# RIGHT_MOTOR.net
KiCad netlist of a schematic drawn in Altium Designer
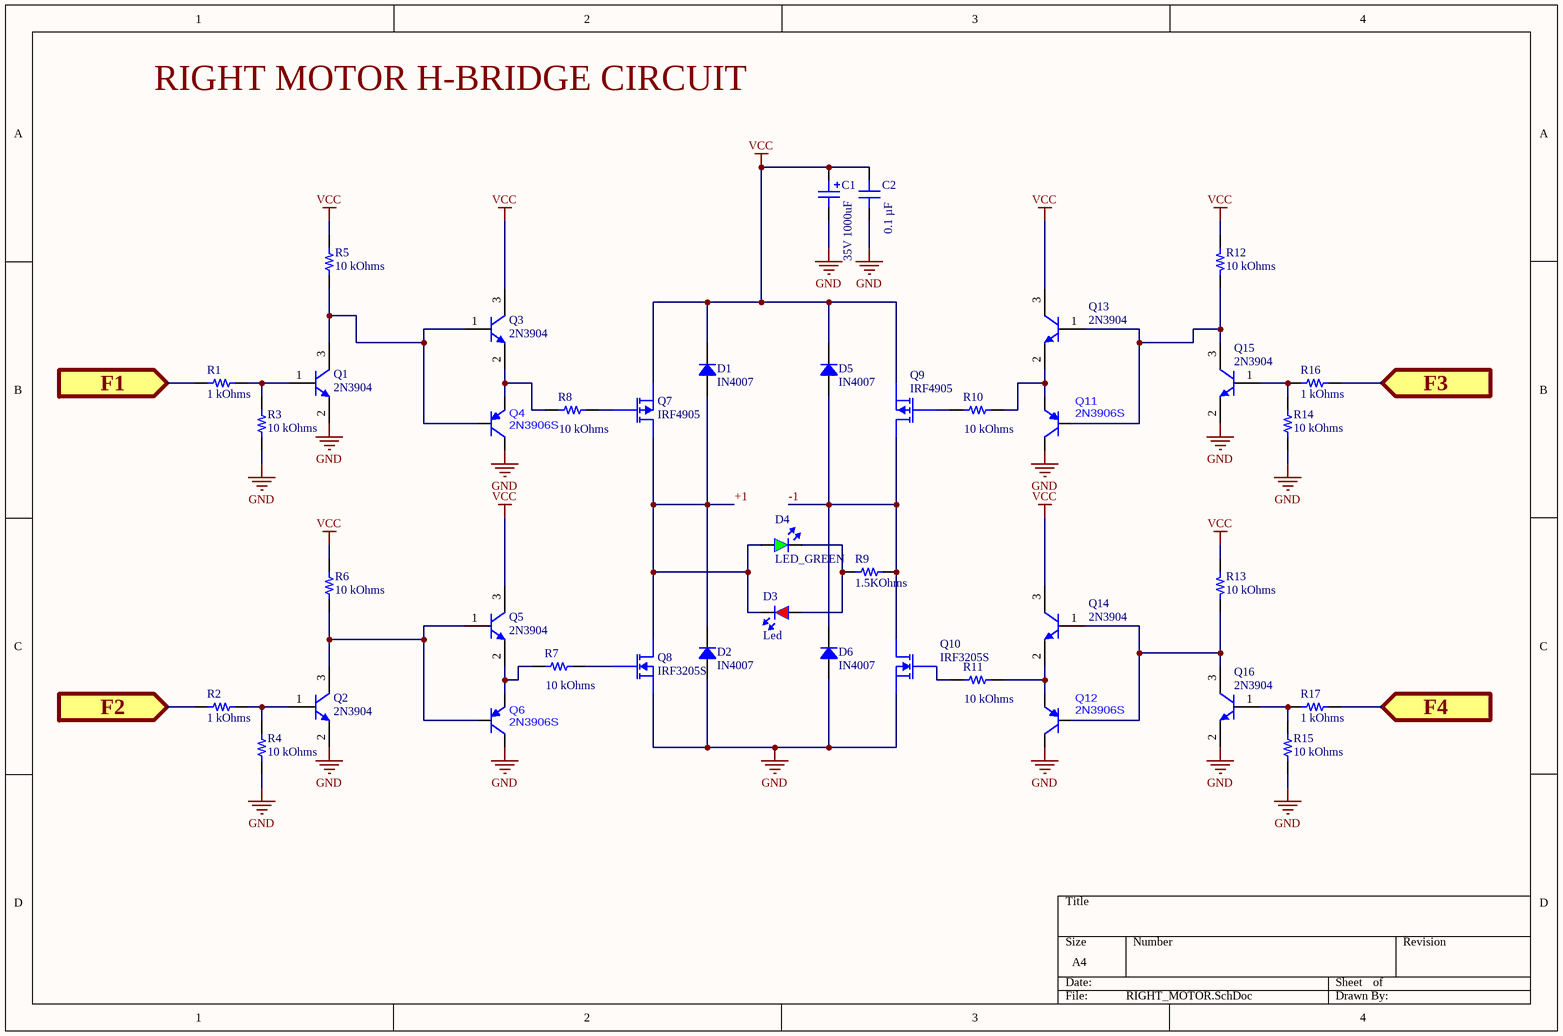
[diagram p0: RIGHT_MOTOR.SchDoc]

(export (version "E")
  (design (tool "Eeschema 10.0.6"))
  (components
    (comp (ref "C1") (value "35V 1000uF") (footprint "35V 1000uF") (libsource (lib "AS") (part "35V 1000uF")))
    (comp (ref "C2")
      (value "0.1 µF")
      (footprint "CAP 1210_3225 - 1MM")
      (description "1210 50VDC 100NF 10% X7R(2R1) AE")
      (fields (field (name "PART NUMBER") "1210Y0500104KST") (field (name "MANUFACTURER") "Knowles Syfer"))
      (libsource (lib "Celestial Altium Library - altium_library") (part "Capacitor"))
    )
    (comp (ref "D1")
      (value "IN4007")
      (footprint "DO214AC SMA")
      (description "DIODE GEN PURP 50V 1A SMA")
      (fields (field (name "PART NUMBER") "RS1A") (field (name "MANUFACTURER") "ON Semiconductor"))
      (libsource (lib "Celestial Altium Library - altium_library") (part "Diode"))
    )
    (comp (ref "D2")
      (value "IN4007")
      (footprint "DO214AC SMA")
      (description "DIODE GEN PURP 50V 1A SMA")
      (fields (field (name "PART NUMBER") "RS1A") (field (name "MANUFACTURER") "ON Semiconductor"))
      (libsource (lib "Celestial Altium Library - altium_library") (part "Diode"))
    )
    (comp (ref "D3") (value "Led") (footprint "LED_RED") (libsource (lib "HBRIDGE") (part "LED_RED_1")))
    (comp (ref "D4")
      (value "LED_GREEN")
      (footprint "LED_GREEN")
      (libsource (lib "HBRIDGE") (part "LED_GREEN"))
    )
    (comp (ref "D5")
      (value "IN4007")
      (footprint "DO214AC SMA")
      (description "DIODE GEN PURP 50V 1A SMA")
      (fields (field (name "PART NUMBER") "RS1A") (field (name "MANUFACTURER") "ON Semiconductor"))
      (libsource (lib "Celestial Altium Library - altium_library") (part "Diode"))
    )
    (comp (ref "D6")
      (value "IN4007")
      (footprint "DO214AC SMA")
      (description "DIODE GEN PURP 50V 1A SMA")
      (fields (field (name "PART NUMBER") "RS1A") (field (name "MANUFACTURER") "ON Semiconductor"))
      (libsource (lib "Celestial Altium Library - altium_library") (part "Diode"))
    )
    (comp (ref "Q1")
      (value "2N3904")
      (footprint "DIODES SOT-23-3")
      (description "2N3904 Npn Smd Transistör Sot-23")
      (fields (field (name "PART NUMBER") "MMBT3904-7-F") (field (name "MANUFACTURER") "Diodes Incorporated"))
      (libsource (lib "Celestial Altium Library - altium_library") (part "DIODES INC NPN SOT-23-3"))
    )
    (comp (ref "Q2")
      (value "2N3904")
      (footprint "DIODES SOT-23-3")
      (description "2N3904 Npn Smd Transistör Sot-23")
      (fields (field (name "PART NUMBER") "MMBT3904-7-F") (field (name "MANUFACTURER") "Diodes Incorporated"))
      (libsource (lib "Celestial Altium Library - altium_library") (part "DIODES INC NPN SOT-23-3"))
    )
    (comp (ref "Q3")
      (value "2N3904")
      (footprint "DIODES SOT-23-3")
      (description "2N3904 Npn Smd Transistör Sot-23")
      (fields (field (name "PART NUMBER") "MMBT3904-7-F") (field (name "MANUFACTURER") "Diodes Incorporated"))
      (libsource (lib "Celestial Altium Library - altium_library") (part "DIODES INC NPN SOT-23-3"))
    )
    (comp (ref "Q4") (value "2N3906S") (footprint "SOT23-3") (libsource (lib "") (part "2N3906S_1")))
    (comp (ref "Q5")
      (value "2N3904")
      (footprint "DIODES SOT-23-3")
      (description "2N3904 Npn Smd Transistör Sot-23")
      (fields (field (name "PART NUMBER") "MMBT3904-7-F") (field (name "MANUFACTURER") "Diodes Incorporated"))
      (libsource (lib "Celestial Altium Library - altium_library") (part "DIODES INC NPN SOT-23-3"))
    )
    (comp (ref "Q6") (value "2N3906S") (footprint "SOT23-3") (libsource (lib "") (part "2N3906S_1")))
    (comp (ref "Q7") (value "IRF4905") (footprint "IRF4905") (libsource (lib "AS") (part "IRF4905")))
    (comp (ref "Q8") (value "IRF3205S") (footprint "IRF3205S") (libsource (lib "HBRIDGE") (part "IRF3205S")))
    (comp (ref "Q9") (value "IRF4905") (footprint "IRF4905") (libsource (lib "AS") (part "IRF4905")))
    (comp (ref "Q10") (value "IRF3205S") (footprint "IRF3205S") (libsource (lib "") (part "IRF3205S_1")))
    (comp (ref "Q11") (value "2N3906S") (footprint "SOT23-3") (libsource (lib "HBRIDGE") (part "2N3906S")))
    (comp (ref "Q12") (value "2N3906S") (footprint "SOT23-3") (libsource (lib "HBRIDGE") (part "2N3906S")))
    (comp (ref "Q13")
      (value "2N3904")
      (footprint "DIODES SOT-23-3")
      (description "2N3904 Npn Smd Transistör Sot-23")
      (fields (field (name "PART NUMBER") "MMBT3904-7-F") (field (name "MANUFACTURER") "Diodes Incorporated"))
      (libsource (lib "Celestial Altium Library - altium_library") (part "DIODES INC NPN SOT-23-3"))
    )
    (comp (ref "Q14")
      (value "2N3904")
      (footprint "DIODES SOT-23-3")
      (description "2N3904 Npn Smd Transistör Sot-23")
      (fields (field (name "PART NUMBER") "MMBT3904-7-F") (field (name "MANUFACTURER") "Diodes Incorporated"))
      (libsource (lib "Celestial Altium Library - altium_library") (part "DIODES INC NPN SOT-23-3"))
    )
    (comp (ref "Q15")
      (value "2N3904")
      (footprint "DIODES SOT-23-3")
      (description "2N3904 Npn Smd Transistör Sot-23")
      (fields (field (name "PART NUMBER") "MMBT3904-7-F") (field (name "MANUFACTURER") "Diodes Incorporated"))
      (libsource (lib "Celestial Altium Library - altium_library") (part "DIODES INC NPN SOT-23-3"))
    )
    (comp (ref "Q16")
      (value "2N3904")
      (footprint "DIODES SOT-23-3")
      (description "2N3904 Npn Smd Transistör Sot-23")
      (fields (field (name "PART NUMBER") "MMBT3904-7-F") (field (name "MANUFACTURER") "Diodes Incorporated"))
      (libsource (lib "Celestial Altium Library - altium_library") (part "DIODES INC NPN SOT-23-3"))
    )
    (comp (ref "R1")
      (value "1 kOhms")
      (footprint "RES 1206_3216")
      (description "RES 1K OHM 0.1% 1/8W 1206")
      (fields
        (field (name "PART NUMBER") "RNCS1206BKE1K00")
        (field (name "MANUFACTURER") "Stackpole Electronics Inc")
      )
      (libsource (lib "Celestial Altium Library - altium_library") (part "Resistor"))
    )
    (comp (ref "R2")
      (value "1 kOhms")
      (footprint "RES 1206_3216")
      (description "RES 1K OHM 0.1% 1/8W 1206")
      (fields
        (field (name "PART NUMBER") "RNCS1206BKE1K00")
        (field (name "MANUFACTURER") "Stackpole Electronics Inc")
      )
      (libsource (lib "Celestial Altium Library - altium_library") (part "Resistor"))
    )
    (comp (ref "R3")
      (value "10 kOhms")
      (footprint "RES 1206_3216")
      (description "RES SMD 10K OHM 1% 1/4W 1206")
      (fields
        (field (name "PART NUMBER") "CRG1206F10K")
        (field (name "MANUFACTURER") "TE Connectivity Passive Product")
      )
      (libsource (lib "Celestial Altium Library - altium_library") (part "Resistor"))
    )
    (comp (ref "R4")
      (value "10 kOhms")
      (footprint "RES 1206_3216")
      (description "RES SMD 10K OHM 1% 1/4W 1206")
      (fields
        (field (name "PART NUMBER") "CRG1206F10K")
        (field (name "MANUFACTURER") "TE Connectivity Passive Product")
      )
      (libsource (lib "Celestial Altium Library - altium_library") (part "Resistor"))
    )
    (comp (ref "R5")
      (value "10 kOhms")
      (footprint "RES 1210_3225")
      (description "RES SMD 10K OHM 5% 3/4W 1210")
      (fields (field (name "PART NUMBER") "CRCW121010K0JNEAHP") (field (name "MANUFACTURER") "Vishay Dale"))
      (libsource (lib "Celestial Altium Library - altium_library") (part "Resistor"))
    )
    (comp (ref "R6")
      (value "10 kOhms")
      (footprint "RES 1210_3225")
      (description "RES SMD 10K OHM 5% 3/4W 1210")
      (fields (field (name "PART NUMBER") "CRCW121010K0JNEAHP") (field (name "MANUFACTURER") "Vishay Dale"))
      (libsource (lib "Celestial Altium Library - altium_library") (part "Resistor"))
    )
    (comp (ref "R7")
      (value "10 kOhms")
      (footprint "RES 1210_3225")
      (description "RES 10K OHM 1% 1/2W 1210")
      (fields
        (field (name "PART NUMBER") "RMCF1210FT10K0")
        (field (name "MANUFACTURER") "Stackpole Electronics Inc")
      )
      (libsource (lib "Celestial Altium Library - altium_library") (part "Resistor"))
    )
    (comp (ref "R8")
      (value "10 kOhms")
      (footprint "RES 1210_3225")
      (description "RES 10K OHM 1% 1/2W 1210")
      (fields
        (field (name "PART NUMBER") "RMCF1210FT10K0")
        (field (name "MANUFACTURER") "Stackpole Electronics Inc")
      )
      (libsource (lib "Celestial Altium Library - altium_library") (part "Resistor"))
    )
    (comp (ref "R9")
      (value "1.5KOhms")
      (footprint "RES 1210_3225")
      (description "RES 1.5K OHM 1% 1/2W 1210")
      (fields
        (field (name "PART NUMBER") "RMCF1210FT10K0")
        (field (name "MANUFACTURER") "Stackpole Electronics Inc")
      )
      (libsource (lib "Celestial Altium Library - altium_library") (part "Resistor"))
    )
    (comp (ref "R10")
      (value "10 kOhms")
      (footprint "RES 1210_3225")
      (description "RES 10K OHM 1% 1/2W 1210")
      (fields
        (field (name "PART NUMBER") "RMCF1210FT10K0")
        (field (name "MANUFACTURER") "Stackpole Electronics Inc")
      )
      (libsource (lib "Celestial Altium Library - altium_library") (part "Resistor"))
    )
    (comp (ref "R11")
      (value "10 kOhms")
      (footprint "RES 1210_3225")
      (description "RES 10K OHM 1% 1/2W 1210")
      (fields
        (field (name "PART NUMBER") "RMCF1210FT10K0")
        (field (name "MANUFACTURER") "Stackpole Electronics Inc")
      )
      (libsource (lib "Celestial Altium Library - altium_library") (part "Resistor"))
    )
    (comp (ref "R12")
      (value "10 kOhms")
      (footprint "RES 1210_3225")
      (description "RES SMD 10K OHM 5% 3/4W 1210")
      (fields (field (name "PART NUMBER") "CRCW121010K0JNEAHP") (field (name "MANUFACTURER") "Vishay Dale"))
      (libsource (lib "Celestial Altium Library - altium_library") (part "Resistor"))
    )
    (comp (ref "R13")
      (value "10 kOhms")
      (footprint "RES 1210_3225")
      (description "RES SMD 10K OHM 5% 3/4W 1210")
      (fields (field (name "PART NUMBER") "CRCW121010K0JNEAHP") (field (name "MANUFACTURER") "Vishay Dale"))
      (libsource (lib "Celestial Altium Library - altium_library") (part "Resistor"))
    )
    (comp (ref "R14")
      (value "10 kOhms")
      (footprint "RES 1206_3216")
      (description "RES SMD 10K OHM 1% 1/4W 1206")
      (fields
        (field (name "PART NUMBER") "CRG1206F10K")
        (field (name "MANUFACTURER") "TE Connectivity Passive Product")
      )
      (libsource (lib "Celestial Altium Library - altium_library") (part "Resistor"))
    )
    (comp (ref "R15")
      (value "10 kOhms")
      (footprint "RES 1206_3216")
      (description "RES SMD 10K OHM 1% 1/4W 1206")
      (fields
        (field (name "PART NUMBER") "CRG1206F10K")
        (field (name "MANUFACTURER") "TE Connectivity Passive Product")
      )
      (libsource (lib "Celestial Altium Library - altium_library") (part "Resistor"))
    )
    (comp (ref "R16")
      (value "1 kOhms")
      (footprint "RES 1206_3216")
      (description "RES 1K OHM 0.1% 1/8W 1206")
      (fields
        (field (name "PART NUMBER") "RNCS1206BKE1K00")
        (field (name "MANUFACTURER") "Stackpole Electronics Inc")
      )
      (libsource (lib "Celestial Altium Library - altium_library") (part "Resistor"))
    )
    (comp (ref "R17")
      (value "1 kOhms")
      (footprint "RES 1206_3216")
      (description "RES 1K OHM 0.1% 1/8W 1206")
      (fields
        (field (name "PART NUMBER") "RNCS1206BKE1K00")
        (field (name "MANUFACTURER") "Stackpole Electronics Inc")
      )
      (libsource (lib "Celestial Altium Library - altium_library") (part "Resistor"))
    )
  )
  (nets
    (net (code "1") (name "/+1") (class "Default")
      (node (ref "D1") (pin "1") (pinfunction "1_1") (pintype "passive"))
      (node (ref "D2") (pin "2") (pinfunction "2_2") (pintype "passive"))
      (node (ref "D3") (pin "2") (pinfunction "OUT_2") (pintype "passive"))
      (node (ref "D4") (pin "1") (pinfunction "IN_1") (pintype "passive"))
      (node (ref "Q7") (pin "2") (pinfunction "D_2") (pintype "passive"))
      (node (ref "Q8") (pin "2") (pinfunction "D_2") (pintype "passive"))
    )
    (net (code "2") (name "/-1") (class "Default")
      (node (ref "D5") (pin "1") (pinfunction "1_1") (pintype "passive"))
      (node (ref "D6") (pin "2") (pinfunction "2_2") (pintype "passive"))
      (node (ref "Q10") (pin "2") (pinfunction "D_2") (pintype "passive"))
      (node (ref "Q9") (pin "2") (pinfunction "D_2") (pintype "passive"))
      (node (ref "R9") (pin "2") (pinfunction "2_2") (pintype "passive"))
    )
    (net (code "3") (name "/F1") (class "Default")
      (node (ref "R1") (pin "1") (pinfunction "1_1") (pintype "passive"))
    )
    (net (code "4") (name "/F2") (class "Default")
      (node (ref "R2") (pin "1") (pinfunction "1_1") (pintype "passive"))
    )
    (net (code "5") (name "/F3") (class "Default")
      (node (ref "R16") (pin "2") (pinfunction "2_2") (pintype "passive"))
    )
    (net (code "6") (name "/F4") (class "Default")
      (node (ref "R17") (pin "2") (pinfunction "2_2") (pintype "passive"))
    )
    (net (code "8") (name "GND") (class "Default")
      (node (ref "C1") (pin "2") (pinfunction "out_2") (pintype "passive"))
      (node (ref "C2") (pin "1") (pinfunction "1_1") (pintype "passive"))
      (node (ref "D2") (pin "1") (pinfunction "1_1") (pintype "passive"))
      (node (ref "D6") (pin "1") (pinfunction "1_1") (pintype "passive"))
      (node (ref "Q1") (pin "2") (pinfunction "E_2") (pintype "passive"))
      (node (ref "Q10") (pin "3") (pinfunction "S_3") (pintype "passive"))
      (node (ref "Q11") (pin "3") (pinfunction "C_3") (pintype "passive"))
      (node (ref "Q12") (pin "3") (pinfunction "C_3") (pintype "passive"))
      (node (ref "Q15") (pin "2") (pinfunction "E_2") (pintype "passive"))
      (node (ref "Q16") (pin "2") (pinfunction "E_2") (pintype "passive"))
      (node (ref "Q2") (pin "2") (pinfunction "E_2") (pintype "passive"))
      (node (ref "Q4") (pin "3") (pinfunction "C_3") (pintype "passive"))
      (node (ref "Q6") (pin "3") (pinfunction "C_3") (pintype "passive"))
      (node (ref "Q8") (pin "3") (pinfunction "S_3") (pintype "passive"))
      (node (ref "R14") (pin "1") (pinfunction "1_1") (pintype "passive"))
      (node (ref "R15") (pin "1") (pinfunction "1_1") (pintype "passive"))
      (node (ref "R3") (pin "1") (pinfunction "1_1") (pintype "passive"))
      (node (ref "R4") (pin "1") (pinfunction "1_1") (pintype "passive"))
    )
    (net (code "9") (name "Net-(D3-IN)") (class "Default")
      (node (ref "D3") (pin "1") (pinfunction "IN_1") (pintype "passive"))
      (node (ref "D4") (pin "2") (pinfunction "OUT_2") (pintype "passive"))
      (node (ref "R9") (pin "1") (pinfunction "1_1") (pintype "passive"))
    )
    (net (code "10") (name "Net-(Q1-B)") (class "Default")
      (node (ref "Q1") (pin "1") (pinfunction "B_1") (pintype "passive"))
      (node (ref "R1") (pin "2") (pinfunction "2_2") (pintype "passive"))
      (node (ref "R3") (pin "2") (pinfunction "2_2") (pintype "passive"))
    )
    (net (code "11") (name "Net-(Q1-C)") (class "Default")
      (node (ref "Q1") (pin "3") (pinfunction "C_3") (pintype "passive"))
      (node (ref "Q3") (pin "1") (pinfunction "B_1") (pintype "passive"))
      (node (ref "Q4") (pin "1") (pinfunction "B_1") (pintype "passive"))
      (node (ref "R5") (pin "2") (pinfunction "2_2") (pintype "passive"))
    )
    (net (code "12") (name "Net-(Q2-B)") (class "Default")
      (node (ref "Q2") (pin "1") (pinfunction "B_1") (pintype "passive"))
      (node (ref "R2") (pin "2") (pinfunction "2_2") (pintype "passive"))
      (node (ref "R4") (pin "2") (pinfunction "2_2") (pintype "passive"))
    )
    (net (code "13") (name "Net-(Q2-C)") (class "Default")
      (node (ref "Q2") (pin "3") (pinfunction "C_3") (pintype "passive"))
      (node (ref "Q5") (pin "1") (pinfunction "B_1") (pintype "passive"))
      (node (ref "Q6") (pin "1") (pinfunction "B_1") (pintype "passive"))
      (node (ref "R6") (pin "2") (pinfunction "2_2") (pintype "passive"))
    )
    (net (code "14") (name "Net-(Q3-E)") (class "Default")
      (node (ref "Q3") (pin "2") (pinfunction "E_2") (pintype "passive"))
      (node (ref "Q4") (pin "2") (pinfunction "E_2") (pintype "passive"))
      (node (ref "R8") (pin "1") (pinfunction "1_1") (pintype "passive"))
    )
    (net (code "15") (name "Net-(Q5-E)") (class "Default")
      (node (ref "Q5") (pin "2") (pinfunction "E_2") (pintype "passive"))
      (node (ref "Q6") (pin "2") (pinfunction "E_2") (pintype "passive"))
      (node (ref "R7") (pin "1") (pinfunction "1_1") (pintype "passive"))
    )
    (net (code "16") (name "Net-(Q7-G)") (class "Default")
      (node (ref "Q7") (pin "1") (pinfunction "G_1") (pintype "passive"))
      (node (ref "R8") (pin "2") (pinfunction "2_2") (pintype "passive"))
    )
    (net (code "17") (name "Net-(Q8-G)") (class "Default")
      (node (ref "Q8") (pin "1") (pinfunction "G_1") (pintype "passive"))
      (node (ref "R7") (pin "2") (pinfunction "2_2") (pintype "passive"))
    )
    (net (code "18") (name "Net-(Q9-G)") (class "Default")
      (node (ref "Q9") (pin "1") (pinfunction "G_1") (pintype "passive"))
      (node (ref "R10") (pin "1") (pinfunction "1_1") (pintype "passive"))
    )
    (net (code "19") (name "Net-(Q10-G)") (class "Default")
      (node (ref "Q10") (pin "1") (pinfunction "G_1") (pintype "passive"))
      (node (ref "R11") (pin "1") (pinfunction "1_1") (pintype "passive"))
    )
    (net (code "20") (name "Net-(Q11-B)") (class "Default")
      (node (ref "Q11") (pin "1") (pinfunction "B_1") (pintype "passive"))
      (node (ref "Q13") (pin "1") (pinfunction "B_1") (pintype "passive"))
      (node (ref "Q15") (pin "3") (pinfunction "C_3") (pintype "passive"))
      (node (ref "R12") (pin "2") (pinfunction "2_2") (pintype "passive"))
    )
    (net (code "21") (name "Net-(Q11-E)") (class "Default")
      (node (ref "Q11") (pin "2") (pinfunction "E_2") (pintype "passive"))
      (node (ref "Q13") (pin "2") (pinfunction "E_2") (pintype "passive"))
      (node (ref "R10") (pin "2") (pinfunction "2_2") (pintype "passive"))
    )
    (net (code "22") (name "Net-(Q12-B)") (class "Default")
      (node (ref "Q12") (pin "1") (pinfunction "B_1") (pintype "passive"))
      (node (ref "Q14") (pin "1") (pinfunction "B_1") (pintype "passive"))
      (node (ref "Q16") (pin "3") (pinfunction "C_3") (pintype "passive"))
      (node (ref "R13") (pin "2") (pinfunction "2_2") (pintype "passive"))
    )
    (net (code "23") (name "Net-(Q12-E)") (class "Default")
      (node (ref "Q12") (pin "2") (pinfunction "E_2") (pintype "passive"))
      (node (ref "Q14") (pin "2") (pinfunction "E_2") (pintype "passive"))
      (node (ref "R11") (pin "2") (pinfunction "2_2") (pintype "passive"))
    )
    (net (code "24") (name "Net-(Q15-B)") (class "Default")
      (node (ref "Q15") (pin "1") (pinfunction "B_1") (pintype "passive"))
      (node (ref "R14") (pin "2") (pinfunction "2_2") (pintype "passive"))
      (node (ref "R16") (pin "1") (pinfunction "1_1") (pintype "passive"))
    )
    (net (code "25") (name "Net-(Q16-B)") (class "Default")
      (node (ref "Q16") (pin "1") (pinfunction "B_1") (pintype "passive"))
      (node (ref "R15") (pin "2") (pinfunction "2_2") (pintype "passive"))
      (node (ref "R17") (pin "1") (pinfunction "1_1") (pintype "passive"))
    )
    (net (code "26") (name "VCC") (class "Default")
      (node (ref "C1") (pin "1") (pinfunction "in_1") (pintype "passive"))
      (node (ref "C2") (pin "2") (pinfunction "2_2") (pintype "passive"))
      (node (ref "D1") (pin "2") (pinfunction "2_2") (pintype "passive"))
      (node (ref "D5") (pin "2") (pinfunction "2_2") (pintype "passive"))
      (node (ref "Q13") (pin "3") (pinfunction "C_3") (pintype "passive"))
      (node (ref "Q14") (pin "3") (pinfunction "C_3") (pintype "passive"))
      (node (ref "Q3") (pin "3") (pinfunction "C_3") (pintype "passive"))
      (node (ref "Q5") (pin "3") (pinfunction "C_3") (pintype "passive"))
      (node (ref "Q7") (pin "3") (pinfunction "S_3") (pintype "passive"))
      (node (ref "Q9") (pin "3") (pinfunction "S_3") (pintype "passive"))
      (node (ref "R12") (pin "1") (pinfunction "1_1") (pintype "passive"))
      (node (ref "R13") (pin "1") (pinfunction "1_1") (pintype "passive"))
      (node (ref "R5") (pin "1") (pinfunction "1_1") (pintype "passive"))
      (node (ref "R6") (pin "1") (pinfunction "1_1") (pintype "passive"))
    )
  )
)
